# PlusBit_PowerSupply.net
KiCad netlist of a schematic drawn in Altium Designer
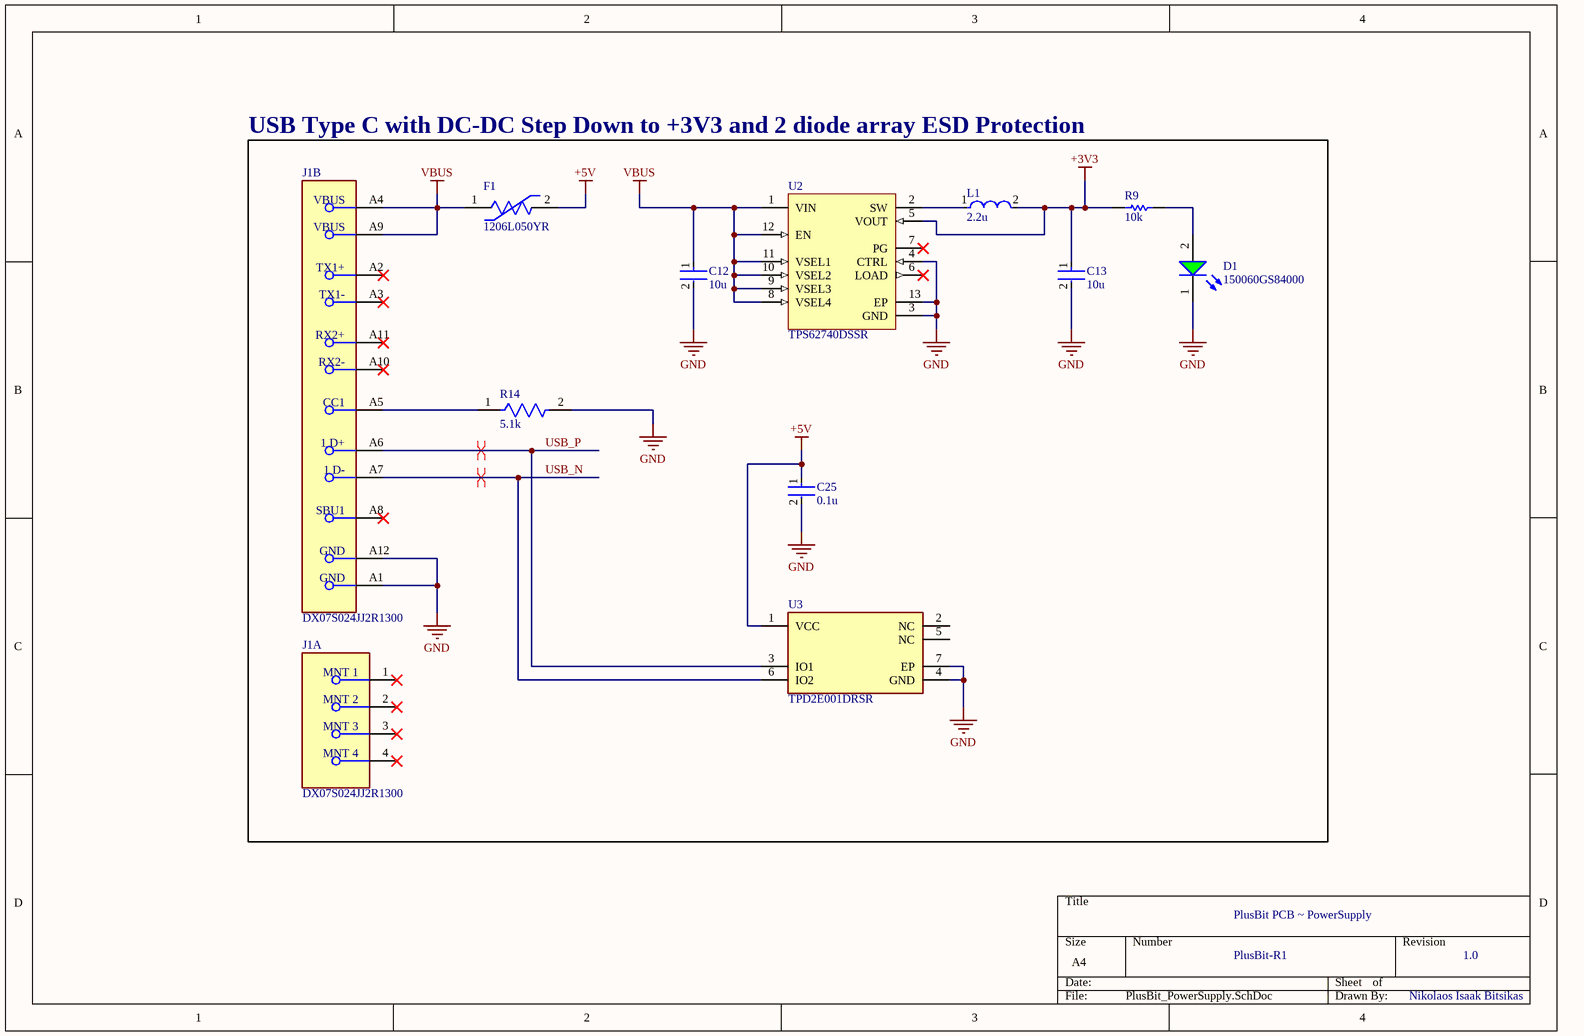
[diagram p0: PlusBit_PowerSupply.SchDoc]

(export (version "E")
  (design (tool "Eeschema 10.0.6"))
  (components
    (comp (ref "C12")
      (value "10u")
      (footprint "FP-GRM188-0_1-e0_2_0_55-IPC_A")
      (description "Chip Multilayer Ceramic Capacitors for General Purpose, 0603, 10uF, X5R, 15%, 20%, 6.3V")
      (fields (field (name "VOLTAGE") "6.3V") (field (name "TOLERANCE") "20%"))
      (libsource (lib "Altium Content Vault") (part "02cd4be3c70576c341d710602a673aa"))
    )
    (comp (ref "C13")
      (value "10u")
      (footprint "FP-GRM188-0_1-e0_2_0_55-IPC_A")
      (description "Chip Multilayer Ceramic Capacitors for General Purpose, 0603, 10uF, X5R, 15%, 20%, 6.3V")
      (fields (field (name "VOLTAGE") "6.3V") (field (name "TOLERANCE") "20%"))
      (libsource (lib "Altium Content Vault") (part "02cd4be3c70576c341d710602a673aa"))
    )
    (comp (ref "C25")
      (value "0.1u")
      (footprint "FP-C0402-BB-MFG")
      (description "CAP CER 0.1UF 16V X7R 0402")
      (fields
        (field (name "TOLERANCE") "0.1")
        (field (name "OCTOPART") "https://octopart.com/c0402c104k4ractu-kemet-94158")
      )
      (libsource (lib "Altium Content Vault") (part "b4654b650e69147ec39a6b967a45e02"))
    )
    (comp (ref "D1")
      (value "150060GS84000")
      (footprint "WL-SMCW_0603_150060xx8x000")
      (description "WL-SMCW SMT Mono-color Chip LED Waterclear")
      (libsource (lib "Altium Content Vault") (part "LED_Green_2A-1K"))
    )
    (comp (ref "F1")
      (value "1206L050YR")
      (footprint "FP-1206L050YR-MFG")
      (description "PTC RESET FUSE 6V 500MA 1206")
      (libsource (lib "Altium Content Vault") (part "fdf083d5f6389a9a1c4e51137f46658"))
    )
    (comp (ref "J1")
      (value "DX07S024JJ2R1300")
      (footprint "FP-DX07S024JJ2R1300-MFG")
      (description "CONN RCP USB3.1 TYPEC 24P SMD RA")
      (libsource (lib "Altium Content Vault") (part "8f50293383fbfcc5c5bbdb5e80e4c84"))
    )
    (comp (ref "L1")
      (value "2.2u")
      (footprint "FP-LQM2HPN_G0-IPC_C")
      (description "Multilayer Type Inductor for Power Lines, 1008 (2520), 2.2μH, 20%, 0.1Ω, 1.3A")
      (fields (field (name "TOLERANCE") "20%"))
      (libsource (lib "Altium Content Vault") (part "725321dda6339637d4d059423bc1c3c"))
    )
    (comp (ref "R9")
      (value "10k")
      (footprint "RESC1608X55X25ML10T15")
      (description "Resistor, 10 KOhm, +/- 5%, 100 mW, -55 to 155 degC, 0603 (1608 Metric), RoHS, Tape and Reel")
      (fields (field (name "MANUFACTURER") "Yageo") (field (name "TOLERANCE") "5%"))
      (libsource (lib "Altium Content Vault") (part "RES-2"))
    )
    (comp (ref "R14")
      (value "5.1k")
      (footprint "FP-CRCW0603-e3-IPC_C")
      (description "RES Thick Film, 5.1kΩ, 1%, 0.1W, 100ppm/°C, 0603")
      (fields (field (name "TOLERANCE") "1%"))
      (libsource (lib "Altium Content Vault") (part "1029c3af85768c4190bb7ad29bc67b5"))
    )
    (comp (ref "U2")
      (value "TPS62740DSSR")
      (footprint "DSS0012A_V")
      (fields (field (name "PARTNUMBER") "TPS62740"))
      (libsource (lib "Altium Content Vault") (part "TI-TPS62740_2-WSON-12"))
    )
    (comp (ref "U3")
      (value "TPD2E001DRSR")
      (footprint "FP-DRS0006A-MFG")
      (description "TVS DIODE 5.5V 6SON")
      (libsource (lib "Altium Content Vault") (part "ecda306b4697849379ff63902f00116"))
    )
  )
  (nets
    (net (code "1") (name "+3V3") (class "Default")
      (node (ref "C13") (pin "1") (pinfunction "1_1") (pintype "passive"))
      (node (ref "L1") (pin "2") (pinfunction "2_2") (pintype "passive"))
      (node (ref "R9") (pin "2") (pinfunction "2_2") (pintype "passive"))
      (node (ref "U2") (pin "5") (pinfunction "VOUT_5") (pintype "input"))
    )
    (net (code "2") (name "+5V") (class "Default")
      (node (ref "C25") (pin "1") (pinfunction "1_1") (pintype "passive"))
      (node (ref "F1") (pin "2") (pinfunction "2_2") (pintype "passive"))
      (node (ref "U3") (pin "1") (pinfunction "VCC_1") (pintype "power_in"))
    )
    (net (code "3") (name "/USB_N") (class "Default")
      (node (ref "J1") (pin "A7") (pinfunction "1_D-_A7") (pintype "passive"))
      (node (ref "U3") (pin "6") (pinfunction "IO2_6") (pintype "passive"))
    )
    (net (code "4") (name "/USB_P") (class "Default")
      (node (ref "J1") (pin "A6") (pinfunction "1_D+_A6") (pintype "passive"))
      (node (ref "U3") (pin "3") (pinfunction "IO1_3") (pintype "passive"))
    )
    (net (code "5") (name "GND") (class "Default")
      (node (ref "C12") (pin "2") (pinfunction "2_2") (pintype "passive"))
      (node (ref "C13") (pin "2") (pinfunction "2_2") (pintype "passive"))
      (node (ref "C25") (pin "2") (pinfunction "2_2") (pintype "passive"))
      (node (ref "D1") (pin "1") (pinfunction "K_1") (pintype "passive"))
      (node (ref "J1") (pin "A1") (pinfunction "GND_A1") (pintype "power_in"))
      (node (ref "J1") (pin "A12") (pinfunction "GND_A12") (pintype "power_in"))
      (node (ref "R14") (pin "2") (pinfunction "2_2") (pintype "passive"))
      (node (ref "U2") (pin "13") (pinfunction "EP_13") (pintype "power_in"))
      (node (ref "U2") (pin "3") (pinfunction "GND_3") (pintype "power_in"))
      (node (ref "U2") (pin "4") (pinfunction "CTRL_4") (pintype "input"))
      (node (ref "U3") (pin "4") (pinfunction "GND_4") (pintype "power_in"))
      (node (ref "U3") (pin "7") (pinfunction "EP_7") (pintype "power_in"))
    )
    (net (code "6") (name "Net-(D1-A)") (class "Default")
      (node (ref "D1") (pin "2") (pinfunction "A_2") (pintype "passive"))
      (node (ref "R9") (pin "1") (pinfunction "1_1") (pintype "passive"))
    )
    (net (code "7") (name "Net-(J1B-CC1)") (class "Default")
      (node (ref "J1") (pin "A5") (pinfunction "CC1_A5") (pintype "passive"))
      (node (ref "R14") (pin "1") (pinfunction "1_1") (pintype "passive"))
    )
    (net (code "8") (name "Net-(U2-SW)") (class "Default")
      (node (ref "L1") (pin "1") (pinfunction "1_1") (pintype "passive"))
      (node (ref "U2") (pin "2") (pinfunction "SW_2") (pintype "power_in"))
    )
    (net (code "9") (name "VBUS") (class "Default")
      (node (ref "C12") (pin "1") (pinfunction "1_1") (pintype "passive"))
      (node (ref "F1") (pin "1") (pinfunction "1_1") (pintype "passive"))
      (node (ref "J1") (pin "A4") (pinfunction "VBUS_A4") (pintype "power_in"))
      (node (ref "J1") (pin "A9") (pinfunction "VBUS_A9") (pintype "passive"))
      (node (ref "U2") (pin "1") (pinfunction "VIN_1") (pintype "power_in"))
      (node (ref "U2") (pin "10") (pinfunction "VSEL2_10") (pintype "input"))
      (node (ref "U2") (pin "11") (pinfunction "VSEL1_11") (pintype "input"))
      (node (ref "U2") (pin "12") (pinfunction "EN_12") (pintype "input"))
      (node (ref "U2") (pin "8") (pinfunction "VSEL4_8") (pintype "input"))
      (node (ref "U2") (pin "9") (pinfunction "VSEL3_9") (pintype "input"))
    )
    (net (code "10") (name "unconnected-(J1A-MNT_1-Pad1)") (class "Default")
      (node (ref "J1") (pin "1") (pinfunction "MNT_1_1") (pintype "passive+no_connect"))
    )
    (net (code "11") (name "unconnected-(J1A-MNT_2-Pad2)") (class "Default")
      (node (ref "J1") (pin "2") (pinfunction "MNT_2_2") (pintype "passive+no_connect"))
    )
    (net (code "12") (name "unconnected-(J1A-MNT_3-Pad3)") (class "Default")
      (node (ref "J1") (pin "3") (pinfunction "MNT_3_3") (pintype "passive+no_connect"))
    )
    (net (code "13") (name "unconnected-(J1A-MNT_4-Pad4)") (class "Default")
      (node (ref "J1") (pin "4") (pinfunction "MNT_4_4") (pintype "passive+no_connect"))
    )
    (net (code "14") (name "unconnected-(J1B-RX2+-PadA11)") (class "Default")
      (node (ref "J1") (pin "A11") (pinfunction "RX2+_A11") (pintype "passive+no_connect"))
    )
    (net (code "15") (name "unconnected-(J1B-RX2--PadA10)") (class "Default")
      (node (ref "J1") (pin "A10") (pinfunction "RX2-_A10") (pintype "passive+no_connect"))
    )
    (net (code "16") (name "unconnected-(J1B-SBU1-PadA8)") (class "Default")
      (node (ref "J1") (pin "A8") (pinfunction "SBU1_A8") (pintype "passive+no_connect"))
    )
    (net (code "17") (name "unconnected-(J1B-TX1+-PadA2)") (class "Default")
      (node (ref "J1") (pin "A2") (pinfunction "TX1+_A2") (pintype "passive+no_connect"))
    )
    (net (code "18") (name "unconnected-(J1B-TX1--PadA3)") (class "Default")
      (node (ref "J1") (pin "A3") (pinfunction "TX1-_A3") (pintype "passive+no_connect"))
    )
    (net (code "19") (name "unconnected-(U2-LOAD-Pad6)") (class "Default")
      (node (ref "U2") (pin "6") (pinfunction "LOAD_6") (pintype "output+no_connect"))
    )
    (net (code "20") (name "unconnected-(U2-PG-Pad7)") (class "Default")
      (node (ref "U2") (pin "7") (pinfunction "PG_7") (pintype "tri_state+no_connect"))
    )
    (net (code "21") (name "unconnected-(U3-NC-Pad2)") (class "Default")
      (node (ref "U3") (pin "2") (pinfunction "NC_2") (pintype "passive"))
    )
    (net (code "22") (name "unconnected-(U3-NC-Pad5)") (class "Default")
      (node (ref "U3") (pin "5") (pinfunction "NC_5") (pintype "passive"))
    )
  )
)
